# OSD.net
KiCad netlist of a schematic drawn in Altium Designer
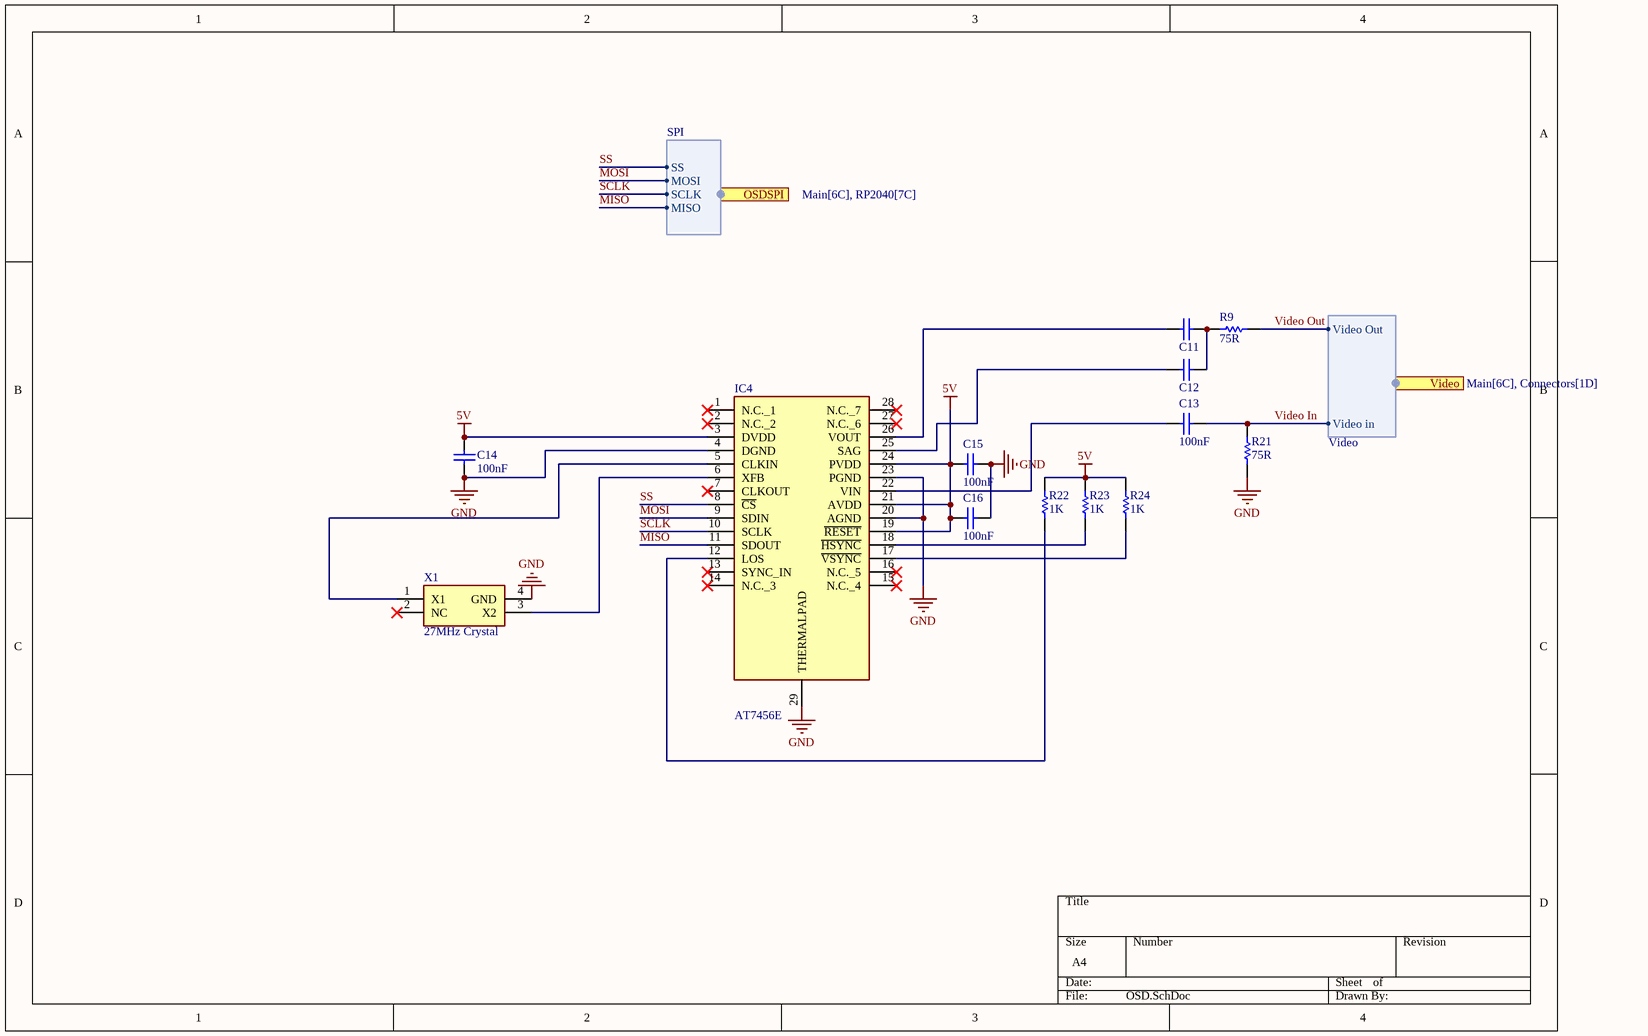
[diagram p0: OSD.SchDoc]

(export (version "E")
  (design (tool "Eeschema 10.0.6"))
  (components
    (comp (ref "C11")
      (value "10µF")
      (footprint "WCAP-CSGP_0603_L1.6W0.8H0.8_Reflow")
      (description "WCAP-CSGP Multilayer Ceramic Chip Capacitor, General Purpose, size 0603, X5R, 10µF, 25VDC")
      (fields
        (field (name "MANUFACTURER PART NUMBER") "885012106031")
        (field (name "MANUFACTURER") "Wurth Elektronik")
      )
      (libsource (lib "Altium_WCAP-CSGP (rev22f)") (part "885012106031"))
    )
    (comp (ref "C12")
      (value "10µF")
      (footprint "WCAP-CSGP_0603_L1.6W0.8H0.8_Reflow")
      (description "WCAP-CSGP Multilayer Ceramic Chip Capacitor, General Purpose, size 0603, X5R, 10µF, 25VDC")
      (fields
        (field (name "MANUFACTURER PART NUMBER") "885012106031")
        (field (name "MANUFACTURER") "Wurth Elektronik")
      )
      (libsource (lib "Altium_WCAP-CSGP (rev22f)") (part "885012106031"))
    )
    (comp (ref "C13")
      (value "100nF")
      (footprint "0402 cap")
      (libsource (lib "Custom Components") (part "Capacitor 0402 100nF"))
    )
    (comp (ref "C14")
      (value "100nF")
      (footprint "0402 cap")
      (libsource (lib "Custom Components") (part "Capacitor 0402 100nF"))
    )
    (comp (ref "C15")
      (value "100nF")
      (footprint "0402 cap")
      (libsource (lib "Custom Components") (part "Capacitor 0402 100nF"))
    )
    (comp (ref "C16")
      (value "100nF")
      (footprint "0402 cap")
      (libsource (lib "Custom Components") (part "Capacitor 0402 100nF"))
    )
    (comp (ref "IC4")
      (value "AT7456E")
      (footprint "SOP65P640X120-29N")
      (description "Integrated Circuit")
      (libsource (lib "Custom Components") (part "AT7456E"))
    )
    (comp (ref "R9")
      (value "75R")
      (footprint "Custom Components:0402 resistor")
      (libsource (lib "Custom Components") (part "Resistor 0402 1K"))
    )
    (comp (ref "R21")
      (value "75R")
      (footprint "Custom Components:0402 resistor")
      (libsource (lib "Custom Components") (part "Resistor 0402 1K"))
    )
    (comp (ref "R22")
      (value "1K")
      (footprint "Custom Components:0402 resistor")
      (libsource (lib "Custom Components") (part "Resistor 0402 1K"))
    )
    (comp (ref "R23")
      (value "1K")
      (footprint "Custom Components:0402 resistor")
      (libsource (lib "Custom Components") (part "Resistor 0402 1K"))
    )
    (comp (ref "R24")
      (value "1K")
      (footprint "Custom Components:0402 resistor")
      (libsource (lib "Custom Components") (part "Resistor 0402 1K"))
    )
    (comp (ref "X1")
      (value "27MHz Crystal")
      (footprint "Custom Components:1612 crystal")
      (description "HD 7E027000H01")
      (fields
        (field (name "MANUFACTURER_PART_NUMBER") "DSC6003MA3B-032K768")
        (field (name "MOUSER PART NUMBER") "579-6003MA3B032K768")
      )
      (libsource (lib "Custom Components") (part "1612 Crystal"))
    )
  )
  (nets
    (net (code "3") (name "/MISO") (class "Default")
      (node (ref "IC4") (pin "11") (pinfunction "SDOUT_11") (pintype "passive"))
    )
    (net (code "4") (name "/MOSI") (class "Default")
      (node (ref "IC4") (pin "9") (pinfunction "SDIN_9") (pintype "passive"))
    )
    (net (code "5") (name "/SCLK") (class "Default")
      (node (ref "IC4") (pin "10") (pinfunction "SCLK_10") (pintype "passive"))
    )
    (net (code "6") (name "/SS") (class "Default")
      (node (ref "IC4") (pin "8") (pinfunction "~{CS}_8") (pintype "passive"))
    )
    (net (code "7") (name "/Video In") (class "Default")
      (node (ref "C13") (pin "2") (pinfunction "2_2") (pintype "passive"))
      (node (ref "R21") (pin "1") (pinfunction "1_1") (pintype "passive"))
    )
    (net (code "8") (name "/Video Out") (class "Default")
      (node (ref "R9") (pin "1") (pinfunction "1_1") (pintype "passive"))
    )
    (net (code "11") (name "5V") (class "Default")
      (node (ref "C14") (pin "2") (pinfunction "2_2") (pintype "passive"))
      (node (ref "C15") (pin "1") (pinfunction "1_1") (pintype "passive"))
      (node (ref "C16") (pin "1") (pinfunction "1_1") (pintype "passive"))
      (node (ref "IC4") (pin "19") (pinfunction "~{RESET}_19") (pintype "passive"))
      (node (ref "IC4") (pin "21") (pinfunction "AVDD_21") (pintype "passive"))
      (node (ref "IC4") (pin "24") (pinfunction "PVDD_24") (pintype "passive"))
      (node (ref "IC4") (pin "3") (pinfunction "DVDD_3") (pintype "passive"))
      (node (ref "R22") (pin "2") (pinfunction "2_2") (pintype "passive"))
      (node (ref "R23") (pin "2") (pinfunction "2_2") (pintype "passive"))
      (node (ref "R24") (pin "2") (pinfunction "2_2") (pintype "passive"))
    )
    (net (code "12") (name "GND") (class "Default")
      (node (ref "C14") (pin "1") (pinfunction "1_1") (pintype "passive"))
      (node (ref "C15") (pin "2") (pinfunction "2_2") (pintype "passive"))
      (node (ref "C16") (pin "2") (pinfunction "2_2") (pintype "passive"))
      (node (ref "IC4") (pin "20") (pinfunction "AGND_20") (pintype "passive"))
      (node (ref "IC4") (pin "23") (pinfunction "PGND_23") (pintype "passive"))
      (node (ref "IC4") (pin "29") (pinfunction "THERMALPAD_29") (pintype "passive"))
      (node (ref "IC4") (pin "4") (pinfunction "DGND_4") (pintype "passive"))
      (node (ref "R21") (pin "2") (pinfunction "2_2") (pintype "passive"))
      (node (ref "X1") (pin "4") (pinfunction "GND_4") (pintype "passive"))
    )
    (net (code "13") (name "Net-(C11-Pad2)") (class "Default")
      (node (ref "C11") (pin "2") (pinfunction "2_2") (pintype "passive"))
      (node (ref "C12") (pin "2") (pinfunction "2_2") (pintype "passive"))
      (node (ref "R9") (pin "2") (pinfunction "2_2") (pintype "passive"))
    )
    (net (code "14") (name "Net-(IC4-CLKIN)") (class "Default")
      (node (ref "IC4") (pin "5") (pinfunction "CLKIN_5") (pintype "passive"))
      (node (ref "X1") (pin "1") (pinfunction "X1_1") (pintype "passive"))
    )
    (net (code "15") (name "Net-(IC4-LOS)") (class "Default")
      (node (ref "IC4") (pin "12") (pinfunction "LOS_12") (pintype "passive"))
      (node (ref "R22") (pin "1") (pinfunction "1_1") (pintype "passive"))
    )
    (net (code "16") (name "Net-(IC4-SAG)") (class "Default")
      (node (ref "C12") (pin "1") (pinfunction "1_1") (pintype "passive"))
      (node (ref "IC4") (pin "25") (pinfunction "SAG_25") (pintype "passive"))
    )
    (net (code "17") (name "Net-(IC4-VIN)") (class "Default")
      (node (ref "C13") (pin "1") (pinfunction "1_1") (pintype "passive"))
      (node (ref "IC4") (pin "22") (pinfunction "VIN_22") (pintype "passive"))
    )
    (net (code "18") (name "Net-(IC4-VOUT)") (class "Default")
      (node (ref "C11") (pin "1") (pinfunction "1_1") (pintype "passive"))
      (node (ref "IC4") (pin "26") (pinfunction "VOUT_26") (pintype "passive"))
    )
    (net (code "19") (name "Net-(IC4-XFB)") (class "Default")
      (node (ref "IC4") (pin "6") (pinfunction "XFB_6") (pintype "passive"))
      (node (ref "X1") (pin "3") (pinfunction "X2_3") (pintype "passive"))
    )
    (net (code "20") (name "Net-(IC4-~{HSYNC})") (class "Default")
      (node (ref "IC4") (pin "18") (pinfunction "~{HSYNC}_18") (pintype "passive"))
      (node (ref "R23") (pin "1") (pinfunction "1_1") (pintype "passive"))
    )
    (net (code "21") (name "Net-(IC4-~{VSYNC})") (class "Default")
      (node (ref "IC4") (pin "17") (pinfunction "~{VSYNC}_17") (pintype "passive"))
      (node (ref "R24") (pin "1") (pinfunction "1_1") (pintype "passive"))
    )
    (net (code "22") (name "unconnected-(IC4-CLKOUT-Pad7)") (class "Default")
      (node (ref "IC4") (pin "7") (pinfunction "CLKOUT_7") (pintype "passive+no_connect"))
    )
    (net (code "23") (name "unconnected-(IC4-N.C._1-Pad1)") (class "Default")
      (node (ref "IC4") (pin "1") (pinfunction "N.C._1_1") (pintype "passive+no_connect"))
    )
    (net (code "24") (name "unconnected-(IC4-N.C._2-Pad2)") (class "Default")
      (node (ref "IC4") (pin "2") (pinfunction "N.C._2_2") (pintype "passive+no_connect"))
    )
    (net (code "25") (name "unconnected-(IC4-N.C._3-Pad14)") (class "Default")
      (node (ref "IC4") (pin "14") (pinfunction "N.C._3_14") (pintype "passive+no_connect"))
    )
    (net (code "26") (name "unconnected-(IC4-N.C._4-Pad15)") (class "Default")
      (node (ref "IC4") (pin "15") (pinfunction "N.C._4_15") (pintype "passive+no_connect"))
    )
    (net (code "27") (name "unconnected-(IC4-N.C._5-Pad16)") (class "Default")
      (node (ref "IC4") (pin "16") (pinfunction "N.C._5_16") (pintype "passive+no_connect"))
    )
    (net (code "28") (name "unconnected-(IC4-N.C._6-Pad27)") (class "Default")
      (node (ref "IC4") (pin "27") (pinfunction "N.C._6_27") (pintype "passive+no_connect"))
    )
    (net (code "29") (name "unconnected-(IC4-N.C._7-Pad28)") (class "Default")
      (node (ref "IC4") (pin "28") (pinfunction "N.C._7_28") (pintype "passive+no_connect"))
    )
    (net (code "30") (name "unconnected-(IC4-SYNC_IN-Pad13)") (class "Default")
      (node (ref "IC4") (pin "13") (pinfunction "SYNC_IN_13") (pintype "passive+no_connect"))
    )
    (net (code "31") (name "unconnected-(X1-NC-Pad2)") (class "Default")
      (node (ref "X1") (pin "2") (pinfunction "NC_2") (pintype "passive+no_connect"))
    )
  )
)
